# Qwiic-RTC.net
KiCad netlist of a schematic drawn in EAGLE
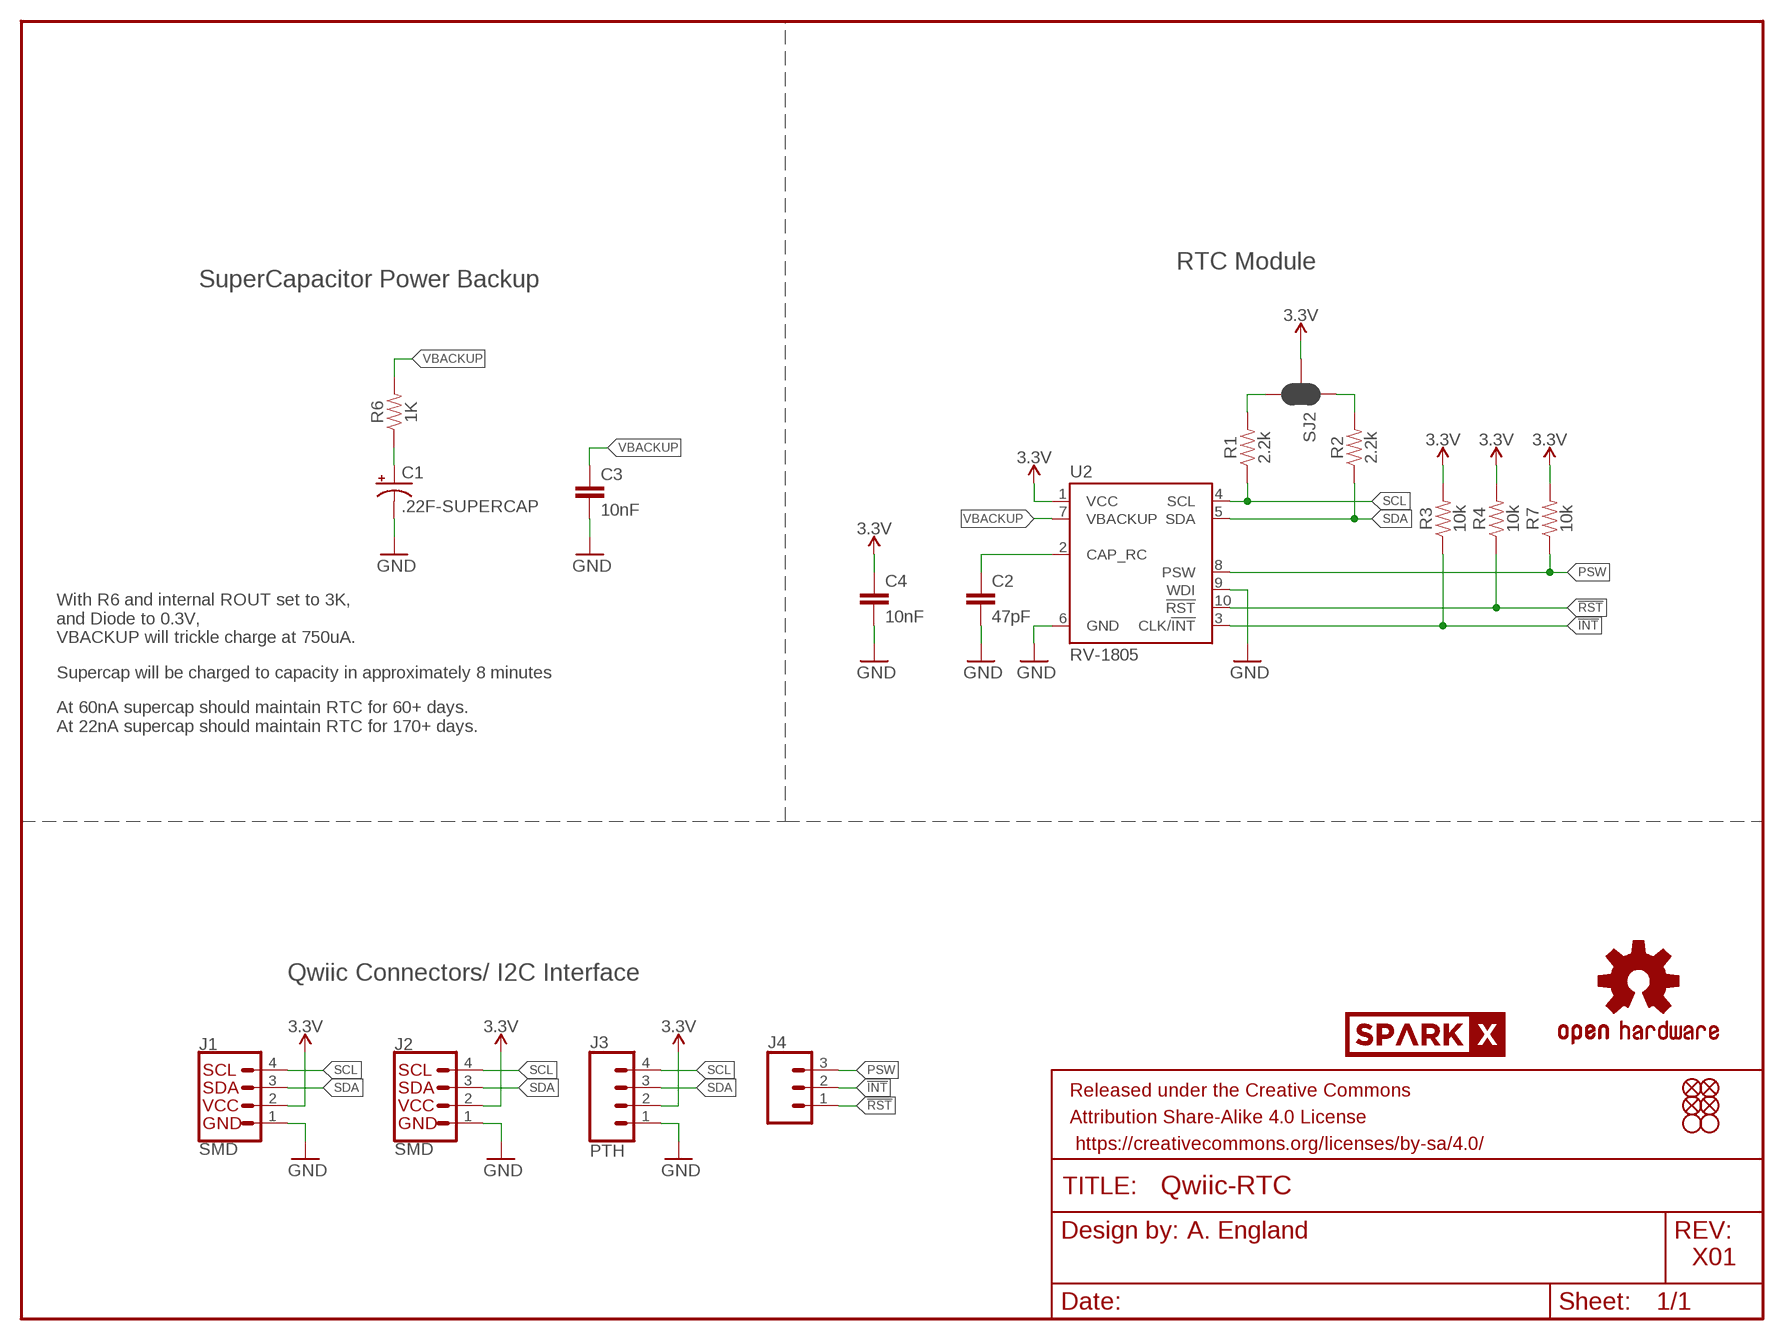
[diagram p0: schematic, sheet 1]

(export (version "E")
  (design (tool "Eeschema 10.0.6"))
  (components
    (comp (ref "C1")
      (value ".22F-SUPERCAP")
      (footprint "eagle-import:DSK-RADIAL-6.8MM")
      (libsource (lib "eagle-import") (part ".22F-SUPERCAP"))
    )
    (comp (ref "C2")
      (value "47pF")
      (footprint "eagle-import:0603")
      (libsource (lib "eagle-import") (part "47PF-0603-50V-5%"))
    )
    (comp (ref "C3")
      (value "10nF")
      (footprint "eagle-import:0603")
      (libsource (lib "eagle-import") (part "10NF-0603-50V-10%"))
    )
    (comp (ref "C4")
      (value "10nF")
      (footprint "eagle-import:0603")
      (libsource (lib "eagle-import") (part "10NF-0603-50V-10%"))
    )
    (comp (ref "FD1")
      (value "FIDUCIALUFIDUCIAL")
      (footprint "eagle-import:FIDUCIAL-MICRO")
      (libsource (lib "eagle-import") (part "FIDUCIALUFIDUCIAL"))
    )
    (comp (ref "FD2")
      (value "FIDUCIALUFIDUCIAL")
      (footprint "eagle-import:FIDUCIAL-MICRO")
      (libsource (lib "eagle-import") (part "FIDUCIALUFIDUCIAL"))
    )
    (comp (ref "FD3")
      (value "FIDUCIALUFIDUCIAL")
      (footprint "eagle-import:FIDUCIAL-MICRO")
      (libsource (lib "eagle-import") (part "FIDUCIALUFIDUCIAL"))
    )
    (comp (ref "FD4")
      (value "FIDUCIALUFIDUCIAL")
      (footprint "eagle-import:FIDUCIAL-MICRO")
      (libsource (lib "eagle-import") (part "FIDUCIALUFIDUCIAL"))
    )
    (comp (ref "FRAME2")
      (value "FRAME-LETTER")
      (footprint "eagle-import:CREATIVE_COMMONS")
      (libsource (lib "eagle-import") (part "FRAME-LETTER"))
    )
    (comp (ref "J1")
      (value "SMD")
      (footprint "eagle-import:1X04_1MM_RA")
      (libsource (lib "eagle-import") (part "QWIIC_CONNECTORJS-1MM"))
    )
    (comp (ref "J2")
      (value "SMD")
      (footprint "eagle-import:1X04_1MM_RA")
      (libsource (lib "eagle-import") (part "QWIIC_CONNECTORJS-1MM"))
    )
    (comp (ref "J3")
      (value "PTH")
      (footprint "eagle-import:1X04_NO_SILK")
      (libsource (lib "eagle-import") (part "CONN_041X04_NO_SILK"))
    )
    (comp (ref "J4")
      (value "CONN_031X03_NO_SILK")
      (footprint "eagle-import:1X03_NO_SILK")
      (libsource (lib "eagle-import") (part "CONN_031X03_NO_SILK"))
    )
    (comp (ref "LOGO1")
      (value "OSHW-LOGOS")
      (footprint "eagle-import:OSHW-LOGO-S")
      (libsource (lib "eagle-import") (part "OSHW-LOGOS"))
    )
    (comp (ref "R1")
      (value "2.2k")
      (footprint "eagle-import:0603")
      (libsource (lib "eagle-import") (part "2.2KOHM-0603-1/10W-1%"))
    )
    (comp (ref "R2")
      (value "2.2k")
      (footprint "eagle-import:0603")
      (libsource (lib "eagle-import") (part "2.2KOHM-0603-1/10W-1%"))
    )
    (comp (ref "R3")
      (value "10k")
      (footprint "eagle-import:0603")
      (libsource (lib "eagle-import") (part "10KOHM-0603-1/10W-1%"))
    )
    (comp (ref "R4")
      (value "10k")
      (footprint "eagle-import:0603")
      (libsource (lib "eagle-import") (part "10KOHM-0603-1/10W-1%"))
    )
    (comp (ref "R6")
      (value "1K")
      (footprint "eagle-import:0603")
      (libsource (lib "eagle-import") (part "2.55KOHM-0603-1/10W-1%"))
    )
    (comp (ref "R7")
      (value "10k")
      (footprint "eagle-import:0603")
      (libsource (lib "eagle-import") (part "10KOHM-0603-1/10W-1%"))
    )
    (comp (ref "SJ2")
      (value "JUMPER-SMT_3_2-NC_PASTE_SILK")
      (footprint "eagle-import:SMT-JUMPER_3_2-NC_PASTE_SILK")
      (libsource (lib "eagle-import") (part "JUMPER-SMT_3_2-NC_PASTE_SILK"))
    )
    (comp (ref "U$3")
      (value "SPARKX-LOGO4")
      (footprint "eagle-import:SPARKX-MEDIUM")
      (libsource (lib "eagle-import") (part "SPARKX-LOGO4"))
    )
    (comp (ref "U$5")
      (value "SPARKX-LOGO4")
      (footprint "eagle-import:SPARKX-MEDIUM")
      (libsource (lib "eagle-import") (part "SPARKX-LOGO4"))
    )
    (comp (ref "U$6")
      (value "STAND-OFF")
      (footprint "eagle-import:STAND-OFF")
      (libsource (lib "eagle-import") (part "STAND-OFF"))
    )
    (comp (ref "U$7")
      (value "STAND-OFF")
      (footprint "eagle-import:STAND-OFF")
      (libsource (lib "eagle-import") (part "STAND-OFF"))
    )
    (comp (ref "U2")
      (value "RV-1805")
      (footprint "eagle-import:RV-1805")
      (libsource (lib "eagle-import") (part "RV-1805"))
    )
  )
  (nets
    (net (code "1") (name "/~{INT}") (class "Default")
      (node (ref "J4") (pin "2") (pinfunction "2_2") (pintype "passive"))
      (node (ref "R3") (pin "1") (pinfunction "1_1") (pintype "passive"))
      (node (ref "U2") (pin "3") (pinfunction "CLK/~{INT}_3") (pintype "bidirectional"))
    )
    (net (code "2") (name "/~{RST}") (class "Default")
      (node (ref "J4") (pin "1") (pinfunction "1_1") (pintype "passive"))
      (node (ref "R4") (pin "1") (pinfunction "1_1") (pintype "passive"))
      (node (ref "U2") (pin "10") (pinfunction "~{RST}_10") (pintype "bidirectional"))
    )
    (net (code "3") (name "3.3V") (class "Default")
      (node (ref "C4") (pin "1") (pinfunction "1_1") (pintype "passive"))
      (node (ref "J1") (pin "2") (pinfunction "2_2") (pintype "power_in"))
      (node (ref "J2") (pin "2") (pinfunction "2_2") (pintype "power_in"))
      (node (ref "J3") (pin "2") (pinfunction "2_2") (pintype "passive"))
      (node (ref "R3") (pin "2") (pinfunction "2_2") (pintype "passive"))
      (node (ref "R4") (pin "2") (pinfunction "2_2") (pintype "passive"))
      (node (ref "R7") (pin "2") (pinfunction "2_2") (pintype "passive"))
      (node (ref "SJ2") (pin "2") (pinfunction "2_2") (pintype "passive"))
      (node (ref "U2") (pin "1") (pinfunction "VCC_1") (pintype "bidirectional"))
    )
    (net (code "4") (name "GND") (class "Default")
      (node (ref "C1") (pin "-") (pinfunction "-_-") (pintype "passive"))
      (node (ref "C2") (pin "2") (pinfunction "2_2") (pintype "passive"))
      (node (ref "C3") (pin "2") (pinfunction "2_2") (pintype "passive"))
      (node (ref "C4") (pin "2") (pinfunction "2_2") (pintype "passive"))
      (node (ref "J1") (pin "1") (pinfunction "1_1") (pintype "power_in"))
      (node (ref "J2") (pin "1") (pinfunction "1_1") (pintype "power_in"))
      (node (ref "J3") (pin "1") (pinfunction "1_1") (pintype "passive"))
      (node (ref "U2") (pin "6") (pinfunction "GND_6") (pintype "bidirectional"))
      (node (ref "U2") (pin "9") (pinfunction "WDI_9") (pintype "bidirectional"))
    )
    (net (code "5") (name "Net-(C1-Pad+)") (class "Default")
      (node (ref "C1") (pin "+") (pinfunction "+_+") (pintype "passive"))
      (node (ref "R6") (pin "1") (pinfunction "1_1") (pintype "passive"))
    )
    (net (code "6") (name "Net-(R1-Pad2)") (class "Default")
      (node (ref "R1") (pin "2") (pinfunction "2_2") (pintype "passive"))
      (node (ref "SJ2") (pin "3") (pinfunction "3_3") (pintype "passive"))
    )
    (net (code "7") (name "Net-(R2-Pad2)") (class "Default")
      (node (ref "R2") (pin "2") (pinfunction "2_2") (pintype "passive"))
      (node (ref "SJ2") (pin "1") (pinfunction "1_1") (pintype "passive"))
    )
    (net (code "8") (name "Net-(U2-CAP_RC)") (class "Default")
      (node (ref "C2") (pin "1") (pinfunction "1_1") (pintype "passive"))
      (node (ref "U2") (pin "2") (pinfunction "CAP_RC_2") (pintype "bidirectional"))
    )
    (net (code "9") (name "PSW") (class "Default")
      (node (ref "J4") (pin "3") (pinfunction "3_3") (pintype "passive"))
      (node (ref "R7") (pin "1") (pinfunction "1_1") (pintype "passive"))
      (node (ref "U2") (pin "8") (pinfunction "PSW_8") (pintype "bidirectional"))
    )
    (net (code "10") (name "SCL") (class "Default")
      (node (ref "J1") (pin "4") (pinfunction "4_4") (pintype "passive"))
      (node (ref "J2") (pin "4") (pinfunction "4_4") (pintype "passive"))
      (node (ref "J3") (pin "4") (pinfunction "4_4") (pintype "passive"))
      (node (ref "R1") (pin "1") (pinfunction "1_1") (pintype "passive"))
      (node (ref "U2") (pin "4") (pinfunction "SCL_4") (pintype "bidirectional"))
    )
    (net (code "11") (name "SDA") (class "Default")
      (node (ref "J1") (pin "3") (pinfunction "3_3") (pintype "passive"))
      (node (ref "J2") (pin "3") (pinfunction "3_3") (pintype "passive"))
      (node (ref "J3") (pin "3") (pinfunction "3_3") (pintype "passive"))
      (node (ref "R2") (pin "1") (pinfunction "1_1") (pintype "passive"))
      (node (ref "U2") (pin "5") (pinfunction "SDA_5") (pintype "bidirectional"))
    )
    (net (code "12") (name "VBACKUP") (class "Default")
      (node (ref "C3") (pin "1") (pinfunction "1_1") (pintype "passive"))
      (node (ref "R6") (pin "2") (pinfunction "2_2") (pintype "passive"))
      (node (ref "U2") (pin "7") (pinfunction "VBACKUP_7") (pintype "bidirectional"))
    )
  )
)
